# motoko_ice_dragon_x_bldc.net
KiCad netlist of a schematic drawn in EAGLE
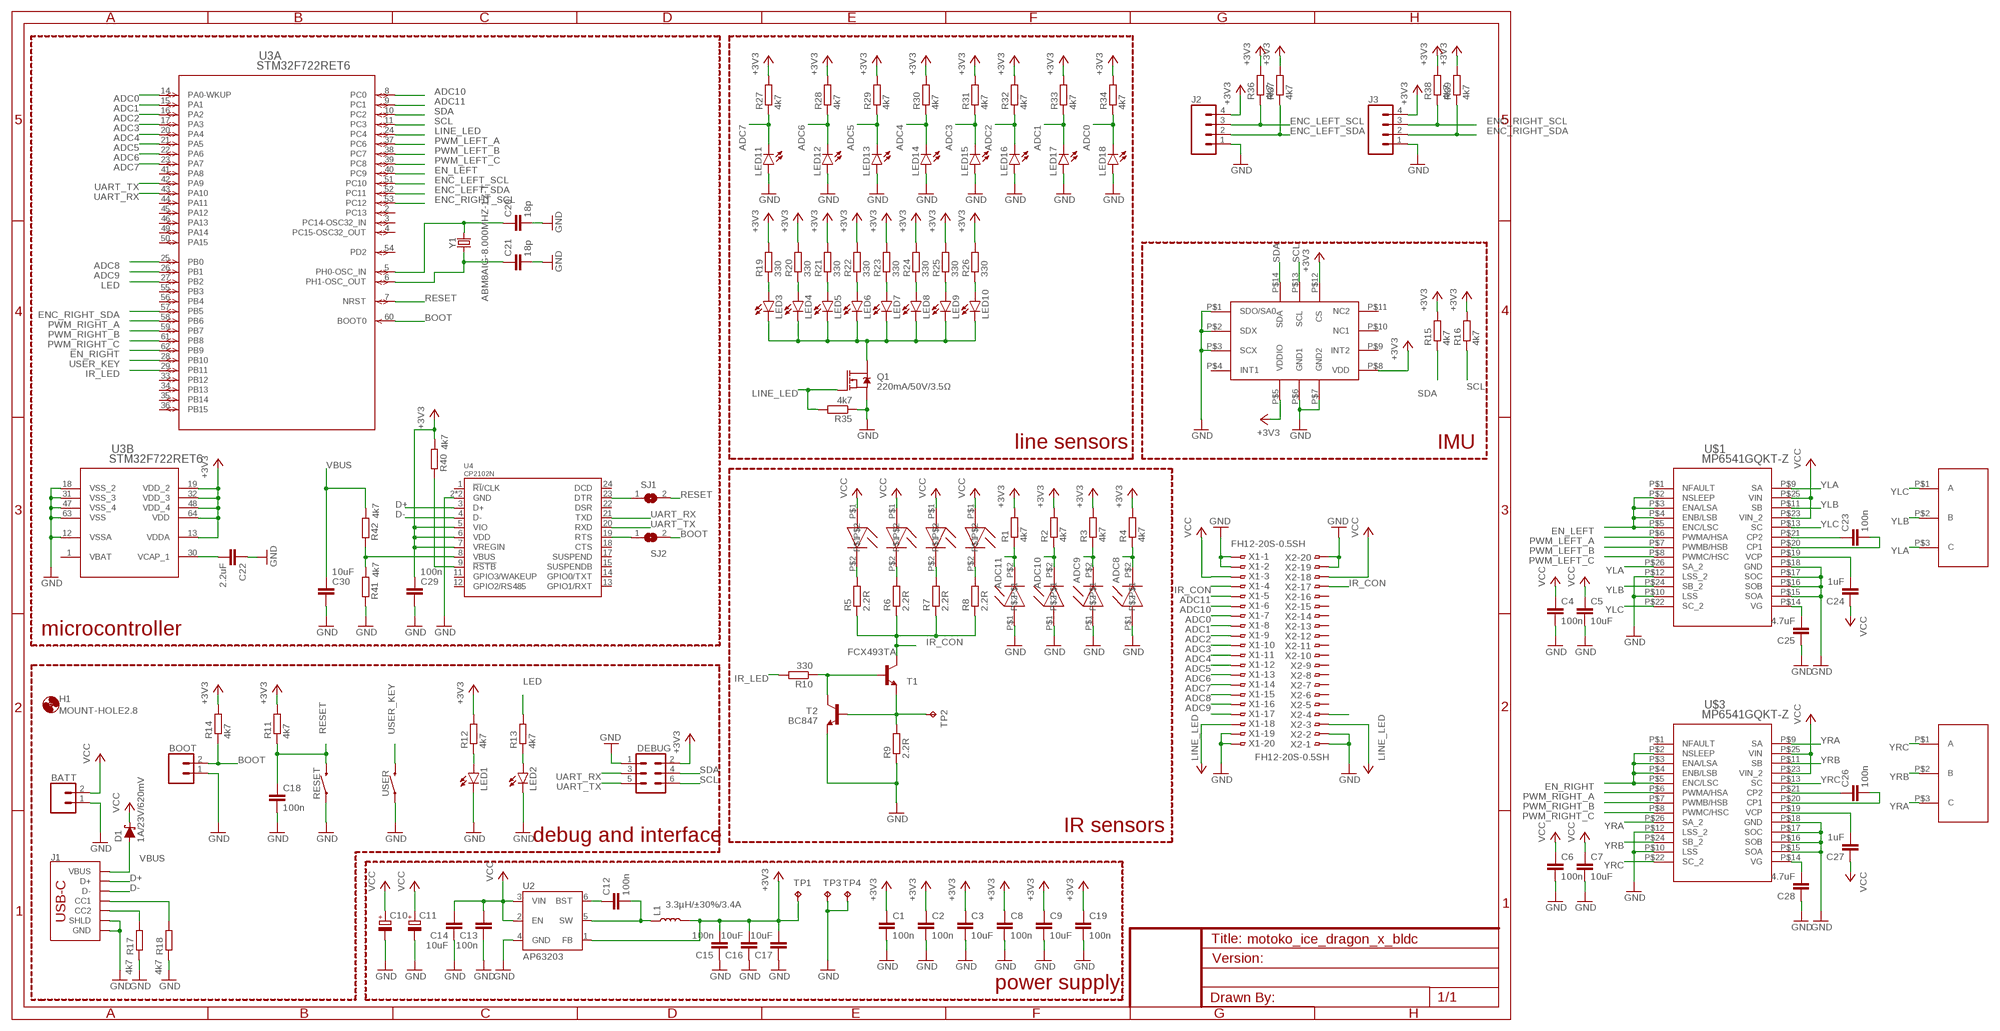
[diagram p0: schematic, sheet 1]

(export (version "E")
  (design (tool "Eeschema 10.0.6"))
  (components
    (comp (ref "BATT")
      (value "CONN_02LOCK_LONGPADS")
      (footprint "eagle-import:1X02_LOCK_LONGPADS")
      (libsource (lib "eagle-import") (part "CONN_02LOCK_LONGPADS"))
    )
    (comp (ref "BOOT")
      (value "CONN_02LOCK_LONGPADS")
      (footprint "eagle-import:1X02_LOCK_LONGPADS")
      (libsource (lib "eagle-import") (part "CONN_02LOCK_LONGPADS"))
    )
    (comp (ref "C1")
      (value "100n")
      (footprint "eagle-import:C0805")
      (libsource (lib "eagle-import") (part "C-EUC0805"))
    )
    (comp (ref "C2")
      (value "100n")
      (footprint "eagle-import:C0805")
      (libsource (lib "eagle-import") (part "C-EUC0805"))
    )
    (comp (ref "C3")
      (value "10uF")
      (footprint "eagle-import:C0805")
      (libsource (lib "eagle-import") (part "C-EUC0805"))
    )
    (comp (ref "C4")
      (value "100n")
      (footprint "eagle-import:C0805")
      (libsource (lib "eagle-import") (part "C-EUC0805"))
    )
    (comp (ref "C5")
      (value "10uF")
      (footprint "eagle-import:C0805")
      (libsource (lib "eagle-import") (part "C-EUC0805"))
    )
    (comp (ref "C6")
      (value "100n")
      (footprint "eagle-import:C0805")
      (libsource (lib "eagle-import") (part "C-EUC0805"))
    )
    (comp (ref "C7")
      (value "10uF")
      (footprint "eagle-import:C0805")
      (libsource (lib "eagle-import") (part "C-EUC0805"))
    )
    (comp (ref "C8")
      (value "100n")
      (footprint "eagle-import:C0805")
      (libsource (lib "eagle-import") (part "C-EUC0805"))
    )
    (comp (ref "C9")
      (value "10uF")
      (footprint "eagle-import:C0805")
      (libsource (lib "eagle-import") (part "C-EUC0805"))
    )
    (comp (ref "C10")
      (value "CPOL-EU140CLH-0810")
      (footprint "eagle-import:140CLH-0810")
      (libsource (lib "eagle-import") (part "CPOL-EU140CLH-0810"))
    )
    (comp (ref "C11")
      (value "CPOL-EU140CLH-0810")
      (footprint "eagle-import:140CLH-0810")
      (libsource (lib "eagle-import") (part "CPOL-EU140CLH-0810"))
    )
    (comp (ref "C12")
      (value "100n")
      (footprint "eagle-import:C0805")
      (libsource (lib "eagle-import") (part "C-EUC0805"))
    )
    (comp (ref "C13")
      (value "100n")
      (footprint "eagle-import:C0805")
      (libsource (lib "eagle-import") (part "C-EUC0805"))
    )
    (comp (ref "C14")
      (value "10uF")
      (footprint "eagle-import:C0805")
      (libsource (lib "eagle-import") (part "C-EUC0805"))
    )
    (comp (ref "C15")
      (value "100n")
      (footprint "eagle-import:C0805")
      (libsource (lib "eagle-import") (part "C-EUC0805"))
    )
    (comp (ref "C16")
      (value "10uF")
      (footprint "eagle-import:C0805")
      (libsource (lib "eagle-import") (part "C-EUC0805"))
    )
    (comp (ref "C17")
      (value "10uF")
      (footprint "eagle-import:C0805")
      (libsource (lib "eagle-import") (part "C-EUC0805"))
    )
    (comp (ref "C18")
      (value "100n")
      (footprint "eagle-import:C0805")
      (libsource (lib "eagle-import") (part "C-EUC0805"))
    )
    (comp (ref "C19")
      (value "100n")
      (footprint "eagle-import:C0805")
      (libsource (lib "eagle-import") (part "C-EUC0805"))
    )
    (comp (ref "C20")
      (value "18p")
      (footprint "eagle-import:C0805")
      (libsource (lib "eagle-import") (part "C-EUC0805"))
    )
    (comp (ref "C21")
      (value "18p")
      (footprint "eagle-import:C0805")
      (libsource (lib "eagle-import") (part "C-EUC0805"))
    )
    (comp (ref "C22")
      (value "2.2uF")
      (footprint "eagle-import:C0805")
      (libsource (lib "eagle-import") (part "C-EUC0805"))
    )
    (comp (ref "C23")
      (value "100n")
      (footprint "eagle-import:C0805")
      (libsource (lib "eagle-import") (part "C-EUC0805"))
    )
    (comp (ref "C24")
      (value "1uF")
      (footprint "eagle-import:C0805")
      (libsource (lib "eagle-import") (part "C-EUC0805"))
    )
    (comp (ref "C25")
      (value "4.7uF")
      (footprint "eagle-import:C0805")
      (libsource (lib "eagle-import") (part "C-EUC0805"))
    )
    (comp (ref "C26")
      (value "100n")
      (footprint "eagle-import:C0805")
      (libsource (lib "eagle-import") (part "C-EUC0805"))
    )
    (comp (ref "C27")
      (value "1uF")
      (footprint "eagle-import:C0805")
      (libsource (lib "eagle-import") (part "C-EUC0805"))
    )
    (comp (ref "C28")
      (value "4.7uF")
      (footprint "eagle-import:C0805")
      (libsource (lib "eagle-import") (part "C-EUC0805"))
    )
    (comp (ref "C29")
      (value "100n")
      (footprint "eagle-import:C0805")
      (libsource (lib "eagle-import") (part "C-EUC0805"))
    )
    (comp (ref "C30")
      (value "10uF")
      (footprint "eagle-import:C0805")
      (libsource (lib "eagle-import") (part "C-EUC0805"))
    )
    (comp (ref "D1")
      (value "1A/23V/620mV")
      (footprint "eagle-import:SOD-323")
      (libsource (lib "eagle-import") (part "DIODE-SCHOTTKY-BAT20J"))
    )
    (comp (ref "DEBUG")
      (value "FEMALE 2x3")
      (footprint "eagle-import:2X3")
      (libsource (lib "eagle-import") (part "CONN_03X2FEMALE"))
    )
    (comp (ref "H1")
      (value "MOUNT-HOLE2.8")
      (footprint "eagle-import:2,8")
      (libsource (lib "eagle-import") (part "MOUNT-HOLE2.8"))
    )
    (comp (ref "J1")
      (value "640-USB4105-GF-A-120, man. GCT")
      (footprint "eagle-import:USB-C-16P-2LAYER-PADS")
      (libsource (lib "eagle-import") (part "USB_C_2-LAYER_PADS"))
    )
    (comp (ref "J2")
      (value "CONN_04LONGPADS")
      (footprint "eagle-import:1X04_LONGPADS")
      (libsource (lib "eagle-import") (part "CONN_04LONGPADS"))
    )
    (comp (ref "J3")
      (value "CONN_04LONGPADS")
      (footprint "eagle-import:1X04_LONGPADS")
      (libsource (lib "eagle-import") (part "CONN_04LONGPADS"))
    )
    (comp (ref "L1")
      (value "3.3µH/±30%/3.4A")
      (footprint "eagle-import:CR54")
      (libsource (lib "eagle-import") (part "INDUCTOR-CR54-3.3UH"))
    )
    (comp (ref "LED1")
      (value "LEDCHIPLED_1206")
      (footprint "eagle-import:CHIPLED_1206")
      (libsource (lib "eagle-import") (part "LEDCHIPLED_1206"))
    )
    (comp (ref "LED2")
      (value "LEDCHIPLED_1206")
      (footprint "eagle-import:CHIPLED_1206")
      (libsource (lib "eagle-import") (part "LEDCHIPLED_1206"))
    )
    (comp (ref "LED3")
      (value "LEDCHIPLED_1206")
      (footprint "eagle-import:CHIPLED_1206")
      (libsource (lib "eagle-import") (part "LEDCHIPLED_1206"))
    )
    (comp (ref "LED4")
      (value "LEDCHIPLED_1206")
      (footprint "eagle-import:CHIPLED_1206")
      (libsource (lib "eagle-import") (part "LEDCHIPLED_1206"))
    )
    (comp (ref "LED5")
      (value "LEDCHIPLED_1206")
      (footprint "eagle-import:CHIPLED_1206")
      (libsource (lib "eagle-import") (part "LEDCHIPLED_1206"))
    )
    (comp (ref "LED6")
      (value "LEDCHIPLED_1206")
      (footprint "eagle-import:CHIPLED_1206")
      (libsource (lib "eagle-import") (part "LEDCHIPLED_1206"))
    )
    (comp (ref "LED7")
      (value "LEDCHIPLED_1206")
      (footprint "eagle-import:CHIPLED_1206")
      (libsource (lib "eagle-import") (part "LEDCHIPLED_1206"))
    )
    (comp (ref "LED8")
      (value "LEDCHIPLED_1206")
      (footprint "eagle-import:CHIPLED_1206")
      (libsource (lib "eagle-import") (part "LEDCHIPLED_1206"))
    )
    (comp (ref "LED9")
      (value "LEDCHIPLED_1206")
      (footprint "eagle-import:CHIPLED_1206")
      (libsource (lib "eagle-import") (part "LEDCHIPLED_1206"))
    )
    (comp (ref "LED10")
      (value "LEDCHIPLED_1206")
      (footprint "eagle-import:CHIPLED_1206")
      (libsource (lib "eagle-import") (part "LEDCHIPLED_1206"))
    )
    (comp (ref "LED11")
      (value "LEDCHIPLED_1206")
      (footprint "eagle-import:CHIPLED_1206")
      (libsource (lib "eagle-import") (part "LEDCHIPLED_1206"))
    )
    (comp (ref "LED12")
      (value "LEDCHIPLED_1206")
      (footprint "eagle-import:CHIPLED_1206")
      (libsource (lib "eagle-import") (part "LEDCHIPLED_1206"))
    )
    (comp (ref "LED13")
      (value "LEDCHIPLED_1206")
      (footprint "eagle-import:CHIPLED_1206")
      (libsource (lib "eagle-import") (part "LEDCHIPLED_1206"))
    )
    (comp (ref "LED14")
      (value "LEDCHIPLED_1206")
      (footprint "eagle-import:CHIPLED_1206")
      (libsource (lib "eagle-import") (part "LEDCHIPLED_1206"))
    )
    (comp (ref "LED15")
      (value "LEDCHIPLED_1206")
      (footprint "eagle-import:CHIPLED_1206")
      (libsource (lib "eagle-import") (part "LEDCHIPLED_1206"))
    )
    (comp (ref "LED16")
      (value "LEDCHIPLED_1206")
      (footprint "eagle-import:CHIPLED_1206")
      (libsource (lib "eagle-import") (part "LEDCHIPLED_1206"))
    )
    (comp (ref "LED17")
      (value "LEDCHIPLED_1206")
      (footprint "eagle-import:CHIPLED_1206")
      (libsource (lib "eagle-import") (part "LEDCHIPLED_1206"))
    )
    (comp (ref "LED18")
      (value "LEDCHIPLED_1206")
      (footprint "eagle-import:CHIPLED_1206")
      (libsource (lib "eagle-import") (part "LEDCHIPLED_1206"))
    )
    (comp (ref "Q1")
      (value "220mA/50V/3.5Ω")
      (footprint "eagle-import:SOT23-3")
      (libsource (lib "eagle-import") (part "MOSFET-NCH-BSS138"))
    )
    (comp (ref "R1")
      (value "4k7")
      (footprint "eagle-import:M0805")
      (libsource (lib "eagle-import") (part "R-EU_M0805"))
    )
    (comp (ref "R2")
      (value "4k7")
      (footprint "eagle-import:M0805")
      (libsource (lib "eagle-import") (part "R-EU_M0805"))
    )
    (comp (ref "R3")
      (value "4k7")
      (footprint "eagle-import:M0805")
      (libsource (lib "eagle-import") (part "R-EU_M0805"))
    )
    (comp (ref "R4")
      (value "4k7")
      (footprint "eagle-import:M0805")
      (libsource (lib "eagle-import") (part "R-EU_M0805"))
    )
    (comp (ref "R5")
      (value "2.2R")
      (footprint "eagle-import:M0805")
      (libsource (lib "eagle-import") (part "R-EU_M0805"))
    )
    (comp (ref "R6")
      (value "2.2R")
      (footprint "eagle-import:M0805")
      (libsource (lib "eagle-import") (part "R-EU_M0805"))
    )
    (comp (ref "R7")
      (value "2.2R")
      (footprint "eagle-import:M0805")
      (libsource (lib "eagle-import") (part "R-EU_M0805"))
    )
    (comp (ref "R8")
      (value "2.2R")
      (footprint "eagle-import:M0805")
      (libsource (lib "eagle-import") (part "R-EU_M0805"))
    )
    (comp (ref "R9")
      (value "2.2R")
      (footprint "eagle-import:M0805")
      (libsource (lib "eagle-import") (part "R-EU_M0805"))
    )
    (comp (ref "R10")
      (value "330")
      (footprint "eagle-import:M0805")
      (libsource (lib "eagle-import") (part "R-EU_M0805"))
    )
    (comp (ref "R11")
      (value "4k7")
      (footprint "eagle-import:M0805")
      (libsource (lib "eagle-import") (part "R-EU_M0805"))
    )
    (comp (ref "R12")
      (value "4k7")
      (footprint "eagle-import:M0805")
      (libsource (lib "eagle-import") (part "R-EU_M0805"))
    )
    (comp (ref "R13")
      (value "4k7")
      (footprint "eagle-import:M0805")
      (libsource (lib "eagle-import") (part "R-EU_M0805"))
    )
    (comp (ref "R14")
      (value "4k7")
      (footprint "eagle-import:M0805")
      (libsource (lib "eagle-import") (part "R-EU_M0805"))
    )
    (comp (ref "R15")
      (value "4k7")
      (footprint "eagle-import:M0805")
      (libsource (lib "eagle-import") (part "R-EU_M0805"))
    )
    (comp (ref "R16")
      (value "4k7")
      (footprint "eagle-import:M0805")
      (libsource (lib "eagle-import") (part "R-EU_M0805"))
    )
    (comp (ref "R17")
      (value "4k7")
      (footprint "eagle-import:M0805")
      (libsource (lib "eagle-import") (part "R-EU_M0805"))
    )
    (comp (ref "R18")
      (value "4k7")
      (footprint "eagle-import:M0805")
      (libsource (lib "eagle-import") (part "R-EU_M0805"))
    )
    (comp (ref "R19")
      (value "330")
      (footprint "eagle-import:M0805")
      (libsource (lib "eagle-import") (part "R-EU_M0805"))
    )
    (comp (ref "R20")
      (value "330")
      (footprint "eagle-import:M0805")
      (libsource (lib "eagle-import") (part "R-EU_M0805"))
    )
    (comp (ref "R21")
      (value "330")
      (footprint "eagle-import:M0805")
      (libsource (lib "eagle-import") (part "R-EU_M0805"))
    )
    (comp (ref "R22")
      (value "330")
      (footprint "eagle-import:M0805")
      (libsource (lib "eagle-import") (part "R-EU_M0805"))
    )
    (comp (ref "R23")
      (value "330")
      (footprint "eagle-import:M0805")
      (libsource (lib "eagle-import") (part "R-EU_M0805"))
    )
    (comp (ref "R24")
      (value "330")
      (footprint "eagle-import:M0805")
      (libsource (lib "eagle-import") (part "R-EU_M0805"))
    )
    (comp (ref "R25")
      (value "330")
      (footprint "eagle-import:M0805")
      (libsource (lib "eagle-import") (part "R-EU_M0805"))
    )
    (comp (ref "R26")
      (value "330")
      (footprint "eagle-import:M0805")
      (libsource (lib "eagle-import") (part "R-EU_M0805"))
    )
    (comp (ref "R27")
      (value "4k7")
      (footprint "eagle-import:M0805")
      (libsource (lib "eagle-import") (part "R-EU_M0805"))
    )
    (comp (ref "R28")
      (value "4k7")
      (footprint "eagle-import:M0805")
      (libsource (lib "eagle-import") (part "R-EU_M0805"))
    )
    (comp (ref "R29")
      (value "4k7")
      (footprint "eagle-import:M0805")
      (libsource (lib "eagle-import") (part "R-EU_M0805"))
    )
    (comp (ref "R30")
      (value "4k7")
      (footprint "eagle-import:M0805")
      (libsource (lib "eagle-import") (part "R-EU_M0805"))
    )
    (comp (ref "R31")
      (value "4k7")
      (footprint "eagle-import:M0805")
      (libsource (lib "eagle-import") (part "R-EU_M0805"))
    )
    (comp (ref "R32")
      (value "4k7")
      (footprint "eagle-import:M0805")
      (libsource (lib "eagle-import") (part "R-EU_M0805"))
    )
    (comp (ref "R33")
      (value "4k7")
      (footprint "eagle-import:M0805")
      (libsource (lib "eagle-import") (part "R-EU_M0805"))
    )
    (comp (ref "R34")
      (value "4k7")
      (footprint "eagle-import:M0805")
      (libsource (lib "eagle-import") (part "R-EU_M0805"))
    )
    (comp (ref "R35")
      (value "4k7")
      (footprint "eagle-import:M0805")
      (libsource (lib "eagle-import") (part "R-EU_M0805"))
    )
    (comp (ref "R36")
      (value "4k7")
      (footprint "eagle-import:M0805")
      (libsource (lib "eagle-import") (part "R-EU_M0805"))
    )
    (comp (ref "R37")
      (value "4k7")
      (footprint "eagle-import:M0805")
      (libsource (lib "eagle-import") (part "R-EU_M0805"))
    )
    (comp (ref "R38")
      (value "4k7")
      (footprint "eagle-import:M0805")
      (libsource (lib "eagle-import") (part "R-EU_M0805"))
    )
    (comp (ref "R39")
      (value "4k7")
      (footprint "eagle-import:M0805")
      (libsource (lib "eagle-import") (part "R-EU_M0805"))
    )
    (comp (ref "R40")
      (value "4k7")
      (footprint "eagle-import:M0805")
      (libsource (lib "eagle-import") (part "R-EU_M0805"))
    )
    (comp (ref "R41")
      (value "4k7")
      (footprint "eagle-import:M0805")
      (libsource (lib "eagle-import") (part "R-EU_M0805"))
    )
    (comp (ref "R42")
      (value "4k7")
      (footprint "eagle-import:M0805")
      (libsource (lib "eagle-import") (part "R-EU_M0805"))
    )
    (comp (ref "RESET")
      (value "MOMENTARY-SWITCH-SPST-SMD-6.2MM-TALL")
      (footprint "eagle-import:TACTILE_SWITCH_SMD_6.2MM_TALL")
      (libsource (lib "eagle-import") (part "MOMENTARY-SWITCH-SPST-SMD-6.2MM-TALL"))
    )
    (comp (ref "SJ1") (value "SJ") (footprint "eagle-import:SJ") (libsource (lib "eagle-import") (part "SJ")))
    (comp (ref "SJ2") (value "SJ") (footprint "eagle-import:SJ") (libsource (lib "eagle-import") (part "SJ")))
    (comp (ref "T1")
      (value "FCX493TA")
      (footprint "eagle-import:SOT89-BCE")
      (libsource (lib "eagle-import") (part "-NPN-SOT89-BCE"))
    )
    (comp (ref "T2")
      (value "BC847")
      (footprint "eagle-import:SOT23")
      (libsource (lib "eagle-import") (part "BC847"))
    )
    (comp (ref "TP1")
      (value "TPB1,27")
      (footprint "eagle-import:B1,27")
      (libsource (lib "eagle-import") (part "TPB1,27"))
    )
    (comp (ref "TP2")
      (value "TPB1,27")
      (footprint "eagle-import:B1,27")
      (libsource (lib "eagle-import") (part "TPB1,27"))
    )
    (comp (ref "TP3")
      (value "TPB1,27")
      (footprint "eagle-import:B1,27")
      (libsource (lib "eagle-import") (part "TPB1,27"))
    )
    (comp (ref "TP4")
      (value "TPB1,27")
      (footprint "eagle-import:B1,27")
      (libsource (lib "eagle-import") (part "TPB1,27"))
    )
    (comp (ref "U$1")
      (value "MP6541GQKT-Z")
      (footprint "eagle-import:TQFN-26")
      (libsource (lib "eagle-import") (part "MP6541GQKT-Z"))
    )
    (comp (ref "U$2")
      (value "BRUSHLESS_GIMBAL_MOTOR_WHEEL")
      (footprint "eagle-import:BRUSHLESS_GIMBAL_MOTOR_WHEEL")
      (libsource (lib "eagle-import") (part "BRUSHLESS_GIMBAL_MOTOR_WHEEL"))
    )
    (comp (ref "U$3")
      (value "MP6541GQKT-Z")
      (footprint "eagle-import:TQFN-26")
      (libsource (lib "eagle-import") (part "MP6541GQKT-Z"))
    )
    (comp (ref "U$4")
      (value "BRUSHLESS_GIMBAL_MOTOR_WHEEL")
      (footprint "eagle-import:BRUSHLESS_GIMBAL_MOTOR_WHEEL")
      (libsource (lib "eagle-import") (part "BRUSHLESS_GIMBAL_MOTOR_WHEEL"))
    )
    (comp (ref "U$6")
      (value "LSM6DSM")
      (footprint "eagle-import:LGA14L")
      (libsource (lib "eagle-import") (part "LSM6DSM"))
    )
    (comp (ref "U$7")
      (value "LED_5MM_AXIAL")
      (footprint "eagle-import:LED_5MM_AXIAL")
      (libsource (lib "eagle-import") (part "LED_5MM_AXIAL"))
    )
    (comp (ref "U$8")
      (value "LED_5MM_AXIAL")
      (footprint "eagle-import:LED_5MM_AXIAL")
      (libsource (lib "eagle-import") (part "LED_5MM_AXIAL"))
    )
    (comp (ref "U$9")
      (value "LED_5MM_AXIAL")
      (footprint "eagle-import:LED_5MM_AXIAL")
      (libsource (lib "eagle-import") (part "LED_5MM_AXIAL"))
    )
    (comp (ref "U$10")
      (value "LED_5MM_AXIAL")
      (footprint "eagle-import:LED_5MM_AXIAL")
      (libsource (lib "eagle-import") (part "LED_5MM_AXIAL"))
    )
    (comp (ref "U$11")
      (value "LED_5MM_AXIAL")
      (footprint "eagle-import:LED_5MM_AXIAL")
      (libsource (lib "eagle-import") (part "LED_5MM_AXIAL"))
    )
    (comp (ref "U$12")
      (value "LED_5MM_AXIAL")
      (footprint "eagle-import:LED_5MM_AXIAL")
      (fields (field (name "SPICEPREFIX") "B"))
      (libsource (lib "eagle-import") (part "LED_5MM_AXIAL"))
    )
    (comp (ref "U$13")
      (value "LED_5MM_AXIAL")
      (footprint "eagle-import:LED_5MM_AXIAL")
      (libsource (lib "eagle-import") (part "LED_5MM_AXIAL"))
    )
    (comp (ref "U$14")
      (value "LED_5MM_AXIAL")
      (footprint "eagle-import:LED_5MM_AXIAL")
      (libsource (lib "eagle-import") (part "LED_5MM_AXIAL"))
    )
    (comp (ref "U2")
      (value "AP63203")
      (footprint "eagle-import:SOT23-6")
      (libsource (lib "eagle-import") (part "AP63203"))
    )
    (comp (ref "U3")
      (value "STM32F722RET6")
      (footprint "eagle-import:LQFP64-10X10MM")
      (fields (field (name "COPYRIGHT") "Copyright (C) 2024 Ultra Librarian. All rights reserved."))
      (libsource (lib "eagle-import") (part "STM32F722RET6"))
    )
    (comp (ref "U4")
      (value "CP2102N")
      (footprint "eagle-import:QFN24")
      (libsource (lib "eagle-import") (part "CP2102N"))
    )
    (comp (ref "USER")
      (value "MOMENTARY-SWITCH-SPST-SMD-6.2MM-TALL")
      (footprint "eagle-import:TACTILE_SWITCH_SMD_6.2MM_TALL")
      (libsource (lib "eagle-import") (part "MOMENTARY-SWITCH-SPST-SMD-6.2MM-TALL"))
    )
    (comp (ref "X1")
      (value "FH12-20S-0.5SH")
      (footprint "eagle-import:FH12-20S-0.5SH")
      (fields (field (name "MPN") "FH12-20S-0.5SH(55)"))
      (libsource (lib "eagle-import") (part "FH12-20S-0.5SH"))
    )
    (comp (ref "X2")
      (value "FH12-20S-0.5SH")
      (footprint "eagle-import:FH12-20S-0.5SH")
      (fields (field (name "MPN") "FH12-20S-0.5SH(55)"))
      (libsource (lib "eagle-import") (part "FH12-20S-0.5SH"))
    )
    (comp (ref "Y1")
      (value "ABM8AIG-8.000MHZ-1Z-T")
      (footprint "eagle-import:CRYSTAL-SMD-3.2X2.5MM")
      (libsource (lib "eagle-import") (part "CRYSTALSMD-3.2X2.5"))
    )
  )
  (nets
    (net (code "1") (name "+3V3") (class "Default")
      (node (ref "C1") (pin "1") (pinfunction "1_1") (pintype "passive"))
      (node (ref "C15") (pin "2") (pinfunction "2_2") (pintype "passive"))
      (node (ref "C16") (pin "2") (pinfunction "2_2") (pintype "passive"))
      (node (ref "C17") (pin "2") (pinfunction "2_2") (pintype "passive"))
      (node (ref "C19") (pin "1") (pinfunction "1_1") (pintype "passive"))
      (node (ref "C2") (pin "1") (pinfunction "1_1") (pintype "passive"))
      (node (ref "C29") (pin "1") (pinfunction "1_1") (pintype "passive"))
      (node (ref "C3") (pin "1") (pinfunction "1_1") (pintype "passive"))
      (node (ref "C8") (pin "1") (pinfunction "1_1") (pintype "passive"))
      (node (ref "C9") (pin "1") (pinfunction "1_1") (pintype "passive"))
      (node (ref "DEBUG") (pin "2") (pinfunction "2_2") (pintype "bidirectional"))
      (node (ref "J2") (pin "4") (pinfunction "4_4") (pintype "passive"))
      (node (ref "J3") (pin "4") (pinfunction "4_4") (pintype "passive"))
      (node (ref "L1") (pin "P$2") (pinfunction "2_P$2") (pintype "passive"))
      (node (ref "R1") (pin "2") (pinfunction "2_2") (pintype "passive"))
      (node (ref "R11") (pin "2") (pinfunction "2_2") (pintype "passive"))
      (node (ref "R12") (pin "2") (pinfunction "2_2") (pintype "passive"))
      (node (ref "R14") (pin "2") (pinfunction "2_2") (pintype "passive"))
      (node (ref "R15") (pin "2") (pinfunction "2_2") (pintype "passive"))
      (node (ref "R16") (pin "2") (pinfunction "2_2") (pintype "passive"))
      (node (ref "R19") (pin "2") (pinfunction "2_2") (pintype "passive"))
      (node (ref "R2") (pin "2") (pinfunction "2_2") (pintype "passive"))
      (node (ref "R20") (pin "2") (pinfunction "2_2") (pintype "passive"))
      (node (ref "R21") (pin "2") (pinfunction "2_2") (pintype "passive"))
      (node (ref "R22") (pin "2") (pinfunction "2_2") (pintype "passive"))
      (node (ref "R23") (pin "2") (pinfunction "2_2") (pintype "passive"))
      (node (ref "R24") (pin "2") (pinfunction "2_2") (pintype "passive"))
      (node (ref "R25") (pin "2") (pinfunction "2_2") (pintype "passive"))
      (node (ref "R26") (pin "2") (pinfunction "2_2") (pintype "passive"))
      (node (ref "R27") (pin "2") (pinfunction "2_2") (pintype "passive"))
      (node (ref "R28") (pin "2") (pinfunction "2_2") (pintype "passive"))
      (node (ref "R29") (pin "2") (pinfunction "2_2") (pintype "passive"))
      (node (ref "R3") (pin "2") (pinfunction "2_2") (pintype "passive"))
      (node (ref "R30") (pin "2") (pinfunction "2_2") (pintype "passive"))
      (node (ref "R31") (pin "2") (pinfunction "2_2") (pintype "passive"))
      (node (ref "R32") (pin "2") (pinfunction "2_2") (pintype "passive"))
      (node (ref "R33") (pin "2") (pinfunction "2_2") (pintype "passive"))
      (node (ref "R34") (pin "2") (pinfunction "2_2") (pintype "passive"))
      (node (ref "R36") (pin "2") (pinfunction "2_2") (pintype "passive"))
      (node (ref "R37") (pin "2") (pinfunction "2_2") (pintype "passive"))
      (node (ref "R38") (pin "2") (pinfunction "2_2") (pintype "passive"))
      (node (ref "R39") (pin "2") (pinfunction "2_2") (pintype "passive"))
      (node (ref "R4") (pin "2") (pinfunction "2_2") (pintype "passive"))
      (node (ref "R40") (pin "1") (pinfunction "1_1") (pintype "passive"))
      (node (ref "TP1") (pin "TP") (pinfunction "TP_TP") (pintype "input"))
      (node (ref "U$6") (pin "P$12") (pinfunction "CS_P$12") (pintype "bidirectional"))
      (node (ref "U$6") (pin "P$5") (pinfunction "VDDIO_P$5") (pintype "bidirectional"))
      (node (ref "U$6") (pin "P$8") (pinfunction "VDD_P$8") (pintype "bidirectional"))
      (node (ref "U2") (pin "1") (pinfunction "FB_1") (pintype "bidirectional"))
      (node (ref "U3") (pin "13") (pinfunction "VDDA_13") (pintype "power_in"))
      (node (ref "U3") (pin "19") (pinfunction "VDD_2_19") (pintype "power_in"))
      (node (ref "U3") (pin "32") (pinfunction "VDD_3_32") (pintype "power_in"))
      (node (ref "U3") (pin "48") (pinfunction "VDD_4_48") (pintype "power_in"))
      (node (ref "U3") (pin "64") (pinfunction "VDD_64") (pintype "power_in"))
      (node (ref "U4") (pin "5") (pinfunction "VIO_5") (pintype "bidirectional"))
      (node (ref "U4") (pin "6") (pinfunction "VDD_6") (pintype "bidirectional"))
      (node (ref "U4") (pin "7") (pinfunction "VREGIN_7") (pintype "bidirectional"))
      (node (ref "X1") (pin "18") (pinfunction "1_18") (pintype "passive"))
      (node (ref "X2") (pin "3") (pinfunction "1_3") (pintype "passive"))
    )
    (net (code "2") (name "/ADC0") (class "Default")
      (node (ref "LED18") (pin "C") (pinfunction "C_C") (pintype "passive"))
      (node (ref "R34") (pin "1") (pinfunction "1_1") (pintype "passive"))
      (node (ref "U3") (pin "14") (pinfunction "PA0-WKUP_14") (pintype "bidirectional"))
      (node (ref "X1") (pin "7") (pinfunction "1_7") (pintype "passive"))
    )
    (net (code "3") (name "/ADC1") (class "Default")
      (node (ref "LED17") (pin "C") (pinfunction "C_C") (pintype "passive"))
      (node (ref "R33") (pin "1") (pinfunction "1_1") (pintype "passive"))
      (node (ref "U3") (pin "15") (pinfunction "PA1_15") (pintype "bidirectional"))
      (node (ref "X1") (pin "8") (pinfunction "1_8") (pintype "passive"))
    )
    (net (code "4") (name "/ADC2") (class "Default")
      (node (ref "LED16") (pin "C") (pinfunction "C_C") (pintype "passive"))
      (node (ref "R32") (pin "1") (pinfunction "1_1") (pintype "passive"))
      (node (ref "U3") (pin "16") (pinfunction "PA2_16") (pintype "bidirectional"))
      (node (ref "X1") (pin "9") (pinfunction "1_9") (pintype "passive"))
    )
    (net (code "5") (name "/ADC3") (class "Default")
      (node (ref "LED15") (pin "C") (pinfunction "C_C") (pintype "passive"))
      (node (ref "R31") (pin "1") (pinfunction "1_1") (pintype "passive"))
      (node (ref "U3") (pin "17") (pinfunction "PA3_17") (pintype "bidirectional"))
      (node (ref "X1") (pin "10") (pinfunction "1_10") (pintype "passive"))
    )
    (net (code "6") (name "/ADC4") (class "Default")
      (node (ref "LED14") (pin "C") (pinfunction "C_C") (pintype "passive"))
      (node (ref "R30") (pin "1") (pinfunction "1_1") (pintype "passive"))
      (node (ref "U3") (pin "20") (pinfunction "PA4_20") (pintype "bidirectional"))
      (node (ref "X1") (pin "11") (pinfunction "1_11") (pintype "passive"))
    )
    (net (code "7") (name "/ADC5") (class "Default")
      (node (ref "LED13") (pin "C") (pinfunction "C_C") (pintype "passive"))
      (node (ref "R29") (pin "1") (pinfunction "1_1") (pintype "passive"))
      (node (ref "U3") (pin "21") (pinfunction "PA5_21") (pintype "bidirectional"))
      (node (ref "X1") (pin "12") (pinfunction "1_12") (pintype "passive"))
    )
    (net (code "8") (name "/ADC6") (class "Default")
      (node (ref "LED12") (pin "C") (pinfunction "C_C") (pintype "passive"))
      (node (ref "R28") (pin "1") (pinfunction "1_1") (pintype "passive"))
      (node (ref "U3") (pin "22") (pinfunction "PA6_22") (pintype "bidirectional"))
      (node (ref "X1") (pin "13") (pinfunction "1_13") (pintype "passive"))
    )
    (net (code "9") (name "/ADC7") (class "Default")
      (node (ref "LED11") (pin "C") (pinfunction "C_C") (pintype "passive"))
      (node (ref "R27") (pin "1") (pinfunction "1_1") (pintype "passive"))
      (node (ref "U3") (pin "23") (pinfunction "PA7_23") (pintype "bidirectional"))
      (node (ref "X1") (pin "14") (pinfunction "1_14") (pintype "passive"))
    )
    (net (code "10") (name "/ADC8") (class "Default")
      (node (ref "R4") (pin "1") (pinfunction "1_1") (pintype "passive"))
      (node (ref "U$7") (pin "P$2") (pinfunction "P$2_P$2") (pintype "bidirectional"))
      (node (ref "U3") (pin "25") (pinfunction "PB0_25") (pintype "bidirectional"))
      (node (ref "X1") (pin "15") (pinfunction "1_15") (pintype "passive"))
    )
    (net (code "11") (name "/ADC9") (class "Default")
      (node (ref "R3") (pin "1") (pinfunction "1_1") (pintype "passive"))
      (node (ref "U$11") (pin "P$2") (pinfunction "P$2_P$2") (pintype "bidirectional"))
      (node (ref "U3") (pin "26") (pinfunction "PB1_26") (pintype "bidirectional"))
      (node (ref "X1") (pin "16") (pinfunction "1_16") (pintype "passive"))
    )
    (net (code "12") (name "/ADC10") (class "Default")
      (node (ref "R2") (pin "1") (pinfunction "1_1") (pintype "passive"))
      (node (ref "U$14") (pin "P$2") (pinfunction "P$2_P$2") (pintype "bidirectional"))
      (node (ref "U3") (pin "8") (pinfunction "PC0_8") (pintype "bidirectional"))
      (node (ref "X1") (pin "6") (pinfunction "1_6") (pintype "passive"))
    )
    (net (code "13") (name "/ADC11") (class "Default")
      (node (ref "R1") (pin "1") (pinfunction "1_1") (pintype "passive"))
      (node (ref "U$9") (pin "P$2") (pinfunction "P$2_P$2") (pintype "bidirectional"))
      (node (ref "U3") (pin "9") (pinfunction "PC1_9") (pintype "bidirectional"))
      (node (ref "X1") (pin "5") (pinfunction "1_5") (pintype "passive"))
    )
    (net (code "14") (name "/BOOT") (class "Default")
      (node (ref "BOOT") (pin "2") (pinfunction "2_2") (pintype "passive"))
      (node (ref "R14") (pin "1") (pinfunction "1_1") (pintype "passive"))
      (node (ref "SJ2") (pin "2") (pinfunction "2_2") (pintype "passive"))
      (node (ref "U3") (pin "60") (pinfunction "BOOT0_60") (pintype "input"))
    )
    (net (code "15") (name "/D+") (class "Default")
      (node (ref "J1") (pin "A6") (pinfunction "D+_A6") (pintype "bidirectional"))
      (node (ref "J1") (pin "B6") (pinfunction "D+_B6") (pintype "bidirectional"))
      (node (ref "U4") (pin "3") (pinfunction "D+_3") (pintype "bidirectional"))
    )
    (net (code "16") (name "/D-") (class "Default")
      (node (ref "J1") (pin "A7") (pinfunction "D-_A7") (pintype "bidirectional"))
      (node (ref "J1") (pin "B7") (pinfunction "D-_B7") (pintype "bidirectional"))
      (node (ref "U4") (pin "4") (pinfunction "D-_4") (pintype "bidirectional"))
    )
    (net (code "17") (name "/ENC_LEFT_SCL") (class "Default")
      (node (ref "J2") (pin "3") (pinfunction "3_3") (pintype "passive"))
      (node (ref "R36") (pin "1") (pinfunction "1_1") (pintype "passive"))
      (node (ref "U3") (pin "51") (pinfunction "PC10_51") (pintype "bidirectional"))
    )
    (net (code "18") (name "/ENC_LEFT_SDA") (class "Default")
      (node (ref "J2") (pin "2") (pinfunction "2_2") (pintype "passive"))
      (node (ref "R37") (pin "1") (pinfunction "1_1") (pintype "passive"))
      (node (ref "U3") (pin "52") (pinfunction "PC11_52") (pintype "bidirectional"))
    )
    (net (code "19") (name "/ENC_RIGHT_SCL") (class "Default")
      (node (ref "J3") (pin "3") (pinfunction "3_3") (pintype "passive"))
      (node (ref "R38") (pin "1") (pinfunction "1_1") (pintype "passive"))
      (node (ref "U3") (pin "53") (pinfunction "PC12_53") (pintype "bidirectional"))
    )
    (net (code "20") (name "/ENC_RIGHT_SDA") (class "Default")
      (node (ref "J3") (pin "2") (pinfunction "2_2") (pintype "passive"))
      (node (ref "R39") (pin "1") (pinfunction "1_1") (pintype "passive"))
      (node (ref "U3") (pin "57") (pinfunction "PB5_57") (pintype "bidirectional"))
    )
    (net (code "21") (name "/EN_LEFT") (class "Default")
      (node (ref "U$1") (pin "P$2") (pinfunction "NSLEEP_P$2") (pintype "input"))
      (node (ref "U$1") (pin "P$3") (pinfunction "ENA/LSA_P$3") (pintype "passive"))
      (node (ref "U$1") (pin "P$4") (pinfunction "ENB/LSB_P$4") (pintype "passive"))
      (node (ref "U$1") (pin "P$5") (pinfunction "ENC/LSC_P$5") (pintype "passive"))
      (node (ref "U3") (pin "40") (pinfunction "PC9_40") (pintype "bidirectional"))
    )
    (net (code "22") (name "/EN_RIGHT") (class "Default")
      (node (ref "U$3") (pin "P$2") (pinfunction "NSLEEP_P$2") (pintype "input"))
      (node (ref "U$3") (pin "P$3") (pinfunction "ENA/LSA_P$3") (pintype "passive"))
      (node (ref "U$3") (pin "P$4") (pinfunction "ENB/LSB_P$4") (pintype "passive"))
      (node (ref "U$3") (pin "P$5") (pinfunction "ENC/LSC_P$5") (pintype "passive"))
      (node (ref "U3") (pin "62") (pinfunction "PB9_62") (pintype "bidirectional"))
    )
    (net (code "23") (name "/IR_CON") (class "Default")
      (node (ref "R5") (pin "1") (pinfunction "1_1") (pintype "passive"))
      (node (ref "R6") (pin "1") (pinfunction "1_1") (pintype "passive"))
      (node (ref "R7") (pin "1") (pinfunction "1_1") (pintype "passive"))
      (node (ref "R8") (pin "1") (pinfunction "1_1") (pintype "passive"))
      (node (ref "T1") (pin "C") (pinfunction "C_C") (pintype "passive"))
      (node (ref "X1") (pin "4") (pinfunction "1_4") (pintype "passive"))
      (node (ref "X2") (pin "17") (pinfunction "1_17") (pintype "passive"))
    )
    (net (code "24") (name "/IR_LED") (class "Default")
      (node (ref "R10") (pin "2") (pinfunction "2_2") (pintype "passive"))
      (node (ref "U3") (pin "29") (pinfunction "PB11_29") (pintype "bidirectional"))
    )
    (net (code "25") (name "/LED") (class "Default")
      (node (ref "R13") (pin "2") (pinfunction "2_2") (pintype "passive"))
      (node (ref "U3") (pin "27") (pinfunction "PB2_27") (pintype "bidirectional"))
    )
    (net (code "26") (name "/LINE_LED") (class "Default")
      (node (ref "Q1") (pin "1") (pinfunction "G_1") (pintype "bidirectional"))
      (node (ref "R35") (pin "2") (pinfunction "2_2") (pintype "passive"))
      (node (ref "U3") (pin "24") (pinfunction "PC4_24") (pintype "bidirectional"))
      (node (ref "X1") (pin "17") (pinfunction "1_17") (pintype "passive"))
      (node (ref "X2") (pin "4") (pinfunction "1_4") (pintype "passive"))
    )
    (net (code "27") (name "/PWM_LEFT_A") (class "Default")
      (node (ref "U$1") (pin "P$6") (pinfunction "PWMA/HSA_P$6") (pintype "passive"))
      (node (ref "U3") (pin "37") (pinfunction "PC6_37") (pintype "bidirectional"))
    )
    (net (code "28") (name "/PWM_LEFT_B") (class "Default")
      (node (ref "U$1") (pin "P$7") (pinfunction "PWMB/HSB_P$7") (pintype "passive"))
      (node (ref "U3") (pin "38") (pinfunction "PC7_38") (pintype "bidirectional"))
    )
    (net (code "29") (name "/PWM_LEFT_C") (class "Default")
      (node (ref "U$1") (pin "P$8") (pinfunction "PWMC/HSC_P$8") (pintype "passive"))
      (node (ref "U3") (pin "39") (pinfunction "PC8_39") (pintype "bidirectional"))
    )
    (net (code "30") (name "/PWM_RIGHT_A") (class "Default")
      (node (ref "U$3") (pin "P$6") (pinfunction "PWMA/HSA_P$6") (pintype "passive"))
      (node (ref "U3") (pin "58") (pinfunction "PB6_58") (pintype "bidirectional"))
    )
    (net (code "31") (name "/PWM_RIGHT_B") (class "Default")
      (node (ref "U$3") (pin "P$7") (pinfunction "PWMB/HSB_P$7") (pintype "passive"))
      (node (ref "U3") (pin "59") (pinfunction "PB7_59") (pintype "bidirectional"))
    )
    (net (code "32") (name "/PWM_RIGHT_C") (class "Default")
      (node (ref "U$3") (pin "P$8") (pinfunction "PWMC/HSC_P$8") (pintype "passive"))
      (node (ref "U3") (pin "61") (pinfunction "PB8_61") (pintype "bidirectional"))
    )
    (net (code "33") (name "/RESET") (class "Default")
      (node (ref "C18") (pin "1") (pinfunction "1_1") (pintype "passive"))
      (node (ref "R11") (pin "1") (pinfunction "1_1") (pintype "passive"))
      (node (ref "RESET") (pin "B2") (pinfunction "2_B2") (pintype "passive"))
      (node (ref "SJ1") (pin "2") (pinfunction "2_2") (pintype "passive"))
      (node (ref "U3") (pin "7") (pinfunction "NRST_7") (pintype "bidirectional"))
    )
    (net (code "34") (name "/SCL") (class "Default")
      (node (ref "DEBUG") (pin "6") (pinfunction "6_6") (pintype "bidirectional"))
      (node (ref "R16") (pin "1") (pinfunction "1_1") (pintype "passive"))
      (node (ref "U$6") (pin "P$13") (pinfunction "SCL_P$13") (pintype "bidirectional"))
      (node (ref "U3") (pin "11") (pinfunction "PC3_11") (pintype "bidirectional"))
    )
    (net (code "35") (name "/SDA") (class "Default")
      (node (ref "DEBUG") (pin "4") (pinfunction "4_4") (pintype "bidirectional"))
      (node (ref "R15") (pin "1") (pinfunction "1_1") (pintype "passive"))
      (node (ref "U$6") (pin "P$14") (pinfunction "SDA_P$14") (pintype "bidirectional"))
      (node (ref "U3") (pin "10") (pinfunction "PC2_10") (pintype "bidirectional"))
    )
    (net (code "36") (name "/UART_RX") (class "Default")
      (node (ref "DEBUG") (pin "3") (pinfunction "3_3") (pintype "bidirectional"))
      (node (ref "U3") (pin "43") (pinfunction "PA10_43") (pintype "bidirectional"))
      (node (ref "U4") (pin "21") (pinfunction "TXD_21") (pintype "bidirectional"))
    )
    (net (code "37") (name "/UART_TX") (class "Default")
      (node (ref "DEBUG") (pin "5") (pinfunction "5_5") (pintype "bidirectional"))
      (node (ref "U3") (pin "42") (pinfunction "PA9_42") (pintype "bidirectional"))
      (node (ref "U4") (pin "20") (pinfunction "RXD_20") (pintype "bidirectional"))
    )
    (net (code "38") (name "/USER_KEY") (class "Default")
      (node (ref "U3") (pin "28") (pinfunction "PB10_28") (pintype "bidirectional"))
      (node (ref "USER") (pin "B2") (pinfunction "2_B2") (pintype "passive"))
    )
    (net (code "39") (name "/VBAT") (class "Default")
      (node (ref "U3") (pin "1") (pinfunction "VBAT_1") (pintype "power_in"))
    )
    (net (code "40") (name "/VBUS") (class "Default")
      (node (ref "C30") (pin "1") (pinfunction "1_1") (pintype "passive"))
      (node (ref "D1") (pin "A") (pinfunction "A_A") (pintype "passive"))
      (node (ref "J1") (pin "VBUS1") (pinfunction "VBUS_VBUS1") (pintype "bidirectional"))
      (node (ref "J1") (pin "VBUS2") (pinfunction "VBUS_VBUS2") (pintype "bidirectional"))
      (node (ref "R42") (pin "1") (pinfunction "1_1") (pintype "passive"))
    )
    (net (code "41") (name "/YLA") (class "Default")
      (node (ref "U$1") (pin "P$26") (pinfunction "SA_2_P$26") (pintype "output"))
      (node (ref "U$1") (pin "P$9") (pinfunction "SA_P$9") (pintype "output"))
      (node (ref "U$2") (pin "P$3") (pinfunction "C_P$3") (pintype "input"))
    )
    (net (code "42") (name "/YLB") (class "Default")
      (node (ref "U$1") (pin "P$11") (pinfunction "SB_P$11") (pintype "output"))
      (node (ref "U$1") (pin "P$24") (pinfunction "SB_2_P$24") (pintype "output"))
      (node (ref "U$2") (pin "P$2") (pinfunction "B_P$2") (pintype "input"))
    )
    (net (code "43") (name "/YLC") (class "Default")
      (node (ref "U$1") (pin "P$13") (pinfunction "SC_P$13") (pintype "output"))
      (node (ref "U$1") (pin "P$22") (pinfunction "SC_2_P$22") (pintype "output"))
      (node (ref "U$2") (pin "P$1") (pinfunction "A_P$1") (pintype "input"))
    )
    (net (code "44") (name "/YRA") (class "Default")
      (node (ref "U$3") (pin "P$26") (pinfunction "SA_2_P$26") (pintype "output"))
      (node (ref "U$3") (pin "P$9") (pinfunction "SA_P$9") (pintype "output"))
      (node (ref "U$4") (pin "P$3") (pinfunction "C_P$3") (pintype "input"))
    )
    (net (code "45") (name "/YRB") (class "Default")
      (node (ref "U$3") (pin "P$11") (pinfunction "SB_P$11") (pintype "output"))
      (node (ref "U$3") (pin "P$24") (pinfunction "SB_2_P$24") (pintype "output"))
      (node (ref "U$4") (pin "P$2") (pinfunction "B_P$2") (pintype "input"))
    )
    (net (code "46") (name "/YRC") (class "Default")
      (node (ref "U$3") (pin "P$13") (pinfunction "SC_P$13") (pintype "output"))
      (node (ref "U$3") (pin "P$22") (pinfunction "SC_2_P$22") (pintype "output"))
      (node (ref "U$4") (pin "P$1") (pinfunction "A_P$1") (pintype "input"))
    )
    (net (code "47") (name "GND") (class "Default")
      (node (ref "BATT") (pin "1") (pinfunction "1_1") (pintype "passive"))
      (node (ref "BOOT") (pin "1") (pinfunction "1_1") (pintype "passive"))
      (node (ref "C1") (pin "2") (pinfunction "2_2") (pintype "passive"))
      (node (ref "C10") (pin "-") (pinfunction "-_-") (pintype "passive"))
      (node (ref "C11") (pin "-") (pinfunction "-_-") (pintype "passive"))
      (node (ref "C13") (pin "1") (pinfunction "1_1") (pintype "passive"))
      (node (ref "C14") (pin "1") (pinfunction "1_1") (pintype "passive"))
      (node (ref "C15") (pin "1") (pinfunction "1_1") (pintype "passive"))
      (node (ref "C16") (pin "1") (pinfunction "1_1") (pintype "passive"))
      (node (ref "C17") (pin "1") (pinfunction "1_1") (pintype "passive"))
      (node (ref "C18") (pin "2") (pinfunction "2_2") (pintype "passive"))
      (node (ref "C19") (pin "2") (pinfunction "2_2") (pintype "passive"))
      (node (ref "C2") (pin "2") (pinfunction "2_2") (pintype "passive"))
      (node (ref "C20") (pin "2") (pinfunction "2_2") (pintype "passive"))
      (node (ref "C21") (pin "2") (pinfunction "2_2") (pintype "passive"))
      (node (ref "C22") (pin "1") (pinfunction "1_1") (pintype "passive"))
      (node (ref "C25") (pin "1") (pinfunction "1_1") (pintype "passive"))
      (node (ref "C28") (pin "1") (pinfunction "1_1") (pintype "passive"))
      (node (ref "C29") (pin "2") (pinfunction "2_2") (pintype "passive"))
      (node (ref "C3") (pin "2") (pinfunction "2_2") (pintype "passive"))
      (node (ref "C30") (pin "2") (pinfunction "2_2") (pintype "passive"))
      (node (ref "C4") (pin "2") (pinfunction "2_2") (pintype "passive"))
      (node (ref "C5") (pin "2") (pinfunction "2_2") (pintype "passive"))
      (node (ref "C6") (pin "2") (pinfunction "2_2") (pintype "passive"))
      (node (ref "C7") (pin "2") (pinfunction "2_2") (pintype "passive"))
      (node (ref "C8") (pin "2") (pinfunction "2_2") (pintype "passive"))
      (node (ref "C9") (pin "2") (pinfunction "2_2") (pintype "passive"))
      (node (ref "DEBUG") (pin "1") (pinfunction "1_1") (pintype "bidirectional"))
      (node (ref "J1") (pin "GND") (pinfunction "GND_GND") (pintype "bidirectional"))
      (node (ref "J1") (pin "GND2") (pinfunction "GND_GND2") (pintype "bidirectional"))
      (node (ref "J1") (pin "SHLD1") (pinfunction "SHLD_SHLD1") (pintype "bidirectional"))
      (node (ref "J1") (pin "SHLD2") (pinfunction "SHLD_SHLD2") (pintype "bidirectional"))
      (node (ref "J1") (pin "SHLD3") (pinfunction "SHLD_SHLD3") (pintype "bidirectional"))
      (node (ref "J1") (pin "SHLD4") (pinfunction "SHLD_SHLD4") (pintype "bidirectional"))
      (node (ref "J2") (pin "1") (pinfunction "1_1") (pintype "passive"))
      (node (ref "J3") (pin "1") (pinfunction "1_1") (pintype "passive"))
      (node (ref "LED1") (pin "C") (pinfunction "C_C") (pintype "passive"))
      (node (ref "LED11") (pin "A") (pinfunction "A_A") (pintype "passive"))
      (node (ref "LED12") (pin "A") (pinfunction "A_A") (pintype "passive"))
      (node (ref "LED13") (pin "A") (pinfunction "A_A") (pintype "passive"))
      (node (ref "LED14") (pin "A") (pinfunction "A_A") (pintype "passive"))
      (node (ref "LED15") (pin "A") (pinfunction "A_A") (pintype "passive"))
      (node (ref "LED16") (pin "A") (pinfunction "A_A") (pintype "passive"))
      (node (ref "LED17") (pin "A") (pinfunction "A_A") (pintype "passive"))
      (node (ref "LED18") (pin "A") (pinfunction "A_A") (pintype "passive"))
      (node (ref "LED2") (pin "C") (pinfunction "C_C") (pintype "passive"))
      (node (ref "Q1") (pin "2") (pinfunction "S_2") (pintype "bidirectional"))
      (node (ref "R17") (pin "1") (pinfunction "1_1") (pintype "passive"))
      (node (ref "R18") (pin "1") (pinfunction "1_1") (pintype "passive"))
      (node (ref "R35") (pin "1") (pinfunction "1_1") (pintype "passive"))
      (node (ref "R41") (pin "2") (pinfunction "2_2") (pintype "passive"))
      (node (ref "R9") (pin "1") (pinfunction "1_1") (pintype "passive"))
      (node (ref "RESET") (pin "A2") (pinfunction "1_A2") (pintype "passive"))
      (node (ref "T2") (pin "2") (pinfunction "E_2") (pintype "passive"))
      (node (ref "TP3") (pin "TP") (pinfunction "TP_TP") (pintype "input"))
      (node (ref "TP4") (pin "TP") (pinfunction "TP_TP") (pintype "input"))
      (node (ref "U$1") (pin "P$10") (pinfunction "LSS_P$10") (pintype "passive"))
      (node (ref "U$1") (pin "P$12") (pinfunction "LSS_2_P$12") (pintype "passive"))
      (node (ref "U$1") (pin "P$15") (pinfunction "SOA_P$15") (pintype "output"))
      (node (ref "U$1") (pin "P$16") (pinfunction "SOB_P$16") (pintype "output"))
      (node (ref "U$1") (pin "P$17") (pinfunction "SOC_P$17") (pintype "output"))
      (node (ref "U$1") (pin "P$18") (pinfunction "GND_P$18") (pintype "passive"))
      (node (ref "U$11") (pin "P$1") (pinfunction "P$1_P$1") (pintype "bidirectional"))
      (node (ref "U$14") (pin "P$1") (pinfunction "P$1_P$1") (pintype "bidirectional"))
      (node (ref "U$3") (pin "P$10") (pinfunction "LSS_P$10") (pintype "passive"))
      (node (ref "U$3") (pin "P$12") (pinfunction "LSS_2_P$12") (pintype "passive"))
      (node (ref "U$3") (pin "P$15") (pinfunction "SOA_P$15") (pintype "output"))
      (node (ref "U$3") (pin "P$16") (pinfunction "SOB_P$16") (pintype "output"))
      (node (ref "U$3") (pin "P$17") (pinfunction "SOC_P$17") (pintype "output"))
      (node (ref "U$3") (pin "P$18") (pinfunction "GND_P$18") (pintype "passive"))
      (node (ref "U$6") (pin "P$1") (pinfunction "SDO/SA0_P$1") (pintype "bidirectional"))
      (node (ref "U$6") (pin "P$2") (pinfunction "SDX_P$2") (pintype "bidirectional"))
      (node (ref "U$6") (pin "P$3") (pinfunction "SCX_P$3") (pintype "bidirectional"))
      (node (ref "U$6") (pin "P$6") (pinfunction "GND1_P$6") (pintype "bidirectional"))
      (node (ref "U$6") (pin "P$7") (pinfunction "GND2_P$7") (pintype "bidirectional"))
      (node (ref "U$7") (pin "P$1") (pinfunction "P$1_P$1") (pintype "bidirectional"))
      (node (ref "U$9") (pin "P$1") (pinfunction "P$1_P$1") (pintype "bidirectional"))
      (node (ref "U2") (pin "4") (pinfunction "GND_4") (pintype "bidirectional"))
      (node (ref "U3") (pin "12") (pinfunction "VSSA_12") (pintype "power_in"))
      (node (ref "U3") (pin "18") (pinfunction "VSS_2_18") (pintype "power_in"))
      (node (ref "U3") (pin "31") (pinfunction "VSS_3_31") (pintype "power_in"))
      (node (ref "U3") (pin "47") (pinfunction "VSS_4_47") (pintype "power_in"))
      (node (ref "U3") (pin "63") (pinfunction "VSS_63") (pintype "power_in"))
      (node (ref "U4") (pin "2") (pinfunction "GND_2") (pintype "bidirectional"))
      (node (ref "U4") (pin "PAD") (pinfunction "GND_PAD") (pintype "bidirectional"))
      (node (ref "USER") (pin "A2") (pinfunction "1_A2") (pintype "passive"))
      (node (ref "X1") (pin "1") (pinfunction "1_1") (pintype "passive"))
      (node (ref "X1") (pin "19") (pinfunction "1_19") (pintype "passive"))
      (node (ref "X1") (pin "2") (pinfunction "1_2") (pintype "passive"))
      (node (ref "X1") (pin "20") (pinfunction "1_20") (pintype "passive"))
      (node (ref "X2") (pin "1") (pinfunction "1_1") (pintype "passive"))
      (node (ref "X2") (pin "19") (pinfunction "1_19") (pintype "passive"))
      (node (ref "X2") (pin "2") (pinfunction "1_2") (pintype "passive"))
      (node (ref "X2") (pin "20") (pinfunction "1_20") (pintype "passive"))
    )
    (net (code "48") (name "Net-(J1-CC1)") (class "Default")
      (node (ref "J1") (pin "A5") (pinfunction "CC1_A5") (pintype "bidirectional"))
      (node (ref "R18") (pin "2") (pinfunction "2_2") (pintype "passive"))
    )
    (net (code "49") (name "Net-(J1-CC2)") (class "Default")
      (node (ref "J1") (pin "B5") (pinfunction "CC2_B5") (pintype "bidirectional"))
      (node (ref "R17") (pin "2") (pinfunction "2_2") (pintype "passive"))
    )
    (net (code "50") (name "Net-(L1-1)") (class "Default")
      (node (ref "C12") (pin "2") (pinfunction "2_2") (pintype "passive"))
      (node (ref "L1") (pin "P$1") (pinfunction "1_P$1") (pintype "passive"))
      (node (ref "U2") (pin "5") (pinfunction "SW_5") (pintype "bidirectional"))
    )
    (net (code "51") (name "Net-(LED1-PadA)") (class "Default")
      (node (ref "LED1") (pin "A") (pinfunction "A_A") (pintype "passive"))
      (node (ref "R12") (pin "1") (pinfunction "1_1") (pintype "passive"))
    )
    (net (code "52") (name "Net-(LED2-PadA)") (class "Default")
      (node (ref "LED2") (pin "A") (pinfunction "A_A") (pintype "passive"))
      (node (ref "R13") (pin "1") (pinfunction "1_1") (pintype "passive"))
    )
    (net (code "53") (name "Net-(LED3-PadA)") (class "Default")
      (node (ref "LED3") (pin "A") (pinfunction "A_A") (pintype "passive"))
      (node (ref "R19") (pin "1") (pinfunction "1_1") (pintype "passive"))
    )
    (net (code "54") (name "Net-(LED4-PadA)") (class "Default")
      (node (ref "LED4") (pin "A") (pinfunction "A_A") (pintype "passive"))
      (node (ref "R20") (pin "1") (pinfunction "1_1") (pintype "passive"))
    )
    (net (code "55") (name "Net-(LED5-PadA)") (class "Default")
      (node (ref "LED5") (pin "A") (pinfunction "A_A") (pintype "passive"))
      (node (ref "R21") (pin "1") (pinfunction "1_1") (pintype "passive"))
    )
    (net (code "56") (name "Net-(LED6-PadA)") (class "Default")
      (node (ref "LED6") (pin "A") (pinfunction "A_A") (pintype "passive"))
      (node (ref "R22") (pin "1") (pinfunction "1_1") (pintype "passive"))
    )
    (net (code "57") (name "Net-(LED7-PadA)") (class "Default")
      (node (ref "LED7") (pin "A") (pinfunction "A_A") (pintype "passive"))
      (node (ref "R23") (pin "1") (pinfunction "1_1") (pintype "passive"))
    )
    (net (code "58") (name "Net-(LED8-PadA)") (class "Default")
      (node (ref "LED8") (pin "A") (pinfunction "A_A") (pintype "passive"))
      (node (ref "R24") (pin "1") (pinfunction "1_1") (pintype "passive"))
    )
    (net (code "59") (name "Net-(LED9-PadA)") (class "Default")
      (node (ref "LED9") (pin "A") (pinfunction "A_A") (pintype "passive"))
      (node (ref "R25") (pin "1") (pinfunction "1_1") (pintype "passive"))
    )
    (net (code "60") (name "Net-(LED10-PadA)") (class "Default")
      (node (ref "LED10") (pin "A") (pinfunction "A_A") (pintype "passive"))
      (node (ref "R26") (pin "1") (pinfunction "1_1") (pintype "passive"))
    )
    (net (code "61") (name "Net-(Q1-D)") (class "Default")
      (node (ref "LED10") (pin "C") (pinfunction "C_C") (pintype "passive"))
      (node (ref "LED3") (pin "C") (pinfunction "C_C") (pintype "passive"))
      (node (ref "LED4") (pin "C") (pinfunction "C_C") (pintype "passive"))
      (node (ref "LED5") (pin "C") (pinfunction "C_C") (pintype "passive"))
      (node (ref "LED6") (pin "C") (pinfunction "C_C") (pintype "passive"))
      (node (ref "LED7") (pin "C") (pinfunction "C_C") (pintype "passive"))
      (node (ref "LED8") (pin "C") (pinfunction "C_C") (pintype "passive"))
      (node (ref "LED9") (pin "C") (pinfunction "C_C") (pintype "passive"))
      (node (ref "Q1") (pin "3") (pinfunction "D_3") (pintype "bidirectional"))
    )
    (net (code "62") (name "Net-(R5-Pad2)") (class "Default")
      (node (ref "R5") (pin "2") (pinfunction "2_2") (pintype "passive"))
      (node (ref "U$10") (pin "P$2") (pinfunction "P$2_P$2") (pintype "bidirectional"))
    )
    (net (code "63") (name "Net-(R6-Pad2)") (class "Default")
      (node (ref "R6") (pin "2") (pinfunction "2_2") (pintype "passive"))
      (node (ref "U$13") (pin "P$2") (pinfunction "P$2_P$2") (pintype "bidirectional"))
    )
    (net (code "64") (name "Net-(R7-Pad2)") (class "Default")
      (node (ref "R7") (pin "2") (pinfunction "2_2") (pintype "passive"))
      (node (ref "U$12") (pin "P$2") (pinfunction "P$2_P$2") (pintype "bidirectional"))
    )
    (net (code "65") (name "Net-(R8-Pad2)") (class "Default")
      (node (ref "R8") (pin "2") (pinfunction "2_2") (pintype "passive"))
      (node (ref "U$8") (pin "P$2") (pinfunction "P$2_P$2") (pintype "bidirectional"))
    )
    (net (code "66") (name "Net-(T2-B)") (class "Default")
      (node (ref "R9") (pin "2") (pinfunction "2_2") (pintype "passive"))
      (node (ref "T1") (pin "E") (pinfunction "E_E") (pintype "passive"))
      (node (ref "T2") (pin "1") (pinfunction "B_1") (pintype "passive"))
      (node (ref "TP2") (pin "TP") (pinfunction "TP_TP") (pintype "input"))
    )
    (net (code "67") (name "Net-(T2-C)") (class "Default")
      (node (ref "R10") (pin "1") (pinfunction "1_1") (pintype "passive"))
      (node (ref "T1") (pin "B") (pinfunction "B_B") (pintype "passive"))
      (node (ref "T2") (pin "3") (pinfunction "C_3") (pintype "passive"))
    )
    (net (code "68") (name "Net-(U$1-CP1)") (class "Default")
      (node (ref "C23") (pin "2") (pinfunction "2_2") (pintype "passive"))
      (node (ref "U$1") (pin "P$20") (pinfunction "CP1_P$20") (pintype "passive"))
    )
    (net (code "69") (name "Net-(U$1-CP2)") (class "Default")
      (node (ref "C23") (pin "1") (pinfunction "1_1") (pintype "passive"))
      (node (ref "U$1") (pin "P$21") (pinfunction "CP2_P$21") (pintype "passive"))
    )
    (net (code "70") (name "Net-(U$1-VCP)") (class "Default")
      (node (ref "C24") (pin "2") (pinfunction "2_2") (pintype "passive"))
      (node (ref "U$1") (pin "P$19") (pinfunction "VCP_P$19") (pintype "output"))
    )
    (net (code "71") (name "Net-(U$1-VG)") (class "Default")
      (node (ref "C25") (pin "2") (pinfunction "2_2") (pintype "passive"))
      (node (ref "U$1") (pin "P$14") (pinfunction "VG_P$14") (pintype "power_in"))
    )
    (net (code "72") (name "Net-(U$3-CP1)") (class "Default")
      (node (ref "C26") (pin "2") (pinfunction "2_2") (pintype "passive"))
      (node (ref "U$3") (pin "P$20") (pinfunction "CP1_P$20") (pintype "passive"))
    )
    (net (code "73") (name "Net-(U$3-CP2)") (class "Default")
      (node (ref "C26") (pin "1") (pinfunction "1_1") (pintype "passive"))
      (node (ref "U$3") (pin "P$21") (pinfunction "CP2_P$21") (pintype "passive"))
    )
    (net (code "74") (name "Net-(U$3-VCP)") (class "Default")
      (node (ref "C27") (pin "2") (pinfunction "2_2") (pintype "passive"))
      (node (ref "U$3") (pin "P$19") (pinfunction "VCP_P$19") (pintype "output"))
    )
    (net (code "75") (name "Net-(U$3-VG)") (class "Default")
      (node (ref "C28") (pin "2") (pinfunction "2_2") (pintype "passive"))
      (node (ref "U$3") (pin "P$14") (pinfunction "VG_P$14") (pintype "power_in"))
    )
    (net (code "76") (name "Net-(U2-BST)") (class "Default")
      (node (ref "C12") (pin "1") (pinfunction "1_1") (pintype "passive"))
      (node (ref "U2") (pin "6") (pinfunction "BST_6") (pintype "bidirectional"))
    )
    (net (code "77") (name "Net-(U3A-PH0-OSC_IN)") (class "Default")
      (node (ref "C20") (pin "1") (pinfunction "1_1") (pintype "passive"))
      (node (ref "U3") (pin "5") (pinfunction "PH0-OSC_IN_5") (pintype "bidirectional"))
      (node (ref "Y1") (pin "3") (pinfunction "2_3") (pintype "passive"))
    )
    (net (code "78") (name "Net-(U3A-PH1-OSC_OUT)") (class "Default")
      (node (ref "C21") (pin "1") (pinfunction "1_1") (pintype "passive"))
      (node (ref "U3") (pin "6") (pinfunction "PH1-OSC_OUT_6") (pintype "bidirectional"))
      (node (ref "Y1") (pin "1") (pinfunction "1_1") (pintype "passive"))
    )
    (net (code "79") (name "Net-(U3B-VCAP_1)") (class "Default")
      (node (ref "C22") (pin "2") (pinfunction "2_2") (pintype "passive"))
      (node (ref "U3") (pin "30") (pinfunction "VCAP_1_30") (pintype "power_in"))
    )
    (net (code "80") (name "Net-(U4-DTR)") (class "Default")
      (node (ref "SJ1") (pin "1") (pinfunction "1_1") (pintype "passive"))
      (node (ref "U4") (pin "23") (pinfunction "DTR_23") (pintype "bidirectional"))
    )
    (net (code "81") (name "Net-(U4-RTS)") (class "Default")
      (node (ref "SJ2") (pin "1") (pinfunction "1_1") (pintype "passive"))
      (node (ref "U4") (pin "19") (pinfunction "RTS_19") (pintype "bidirectional"))
    )
    (net (code "82") (name "Net-(U4-VBUS)") (class "Default")
      (node (ref "R41") (pin "1") (pinfunction "1_1") (pintype "passive"))
      (node (ref "R42") (pin "2") (pinfunction "2_2") (pintype "passive"))
      (node (ref "U4") (pin "8") (pinfunction "VBUS_8") (pintype "bidirectional"))
    )
    (net (code "83") (name "Net-(U4-~{RSTB})") (class "Default")
      (node (ref "R40") (pin "2") (pinfunction "2_2") (pintype "passive"))
      (node (ref "U4") (pin "9") (pinfunction "~{RSTB}_9") (pintype "bidirectional"))
    )
    (net (code "84") (name "VCC") (class "Default")
      (node (ref "BATT") (pin "2") (pinfunction "2_2") (pintype "passive"))
      (node (ref "C10") (pin "+") (pinfunction "+_+") (pintype "passive"))
      (node (ref "C11") (pin "+") (pinfunction "+_+") (pintype "passive"))
      (node (ref "C13") (pin "2") (pinfunction "2_2") (pintype "passive"))
      (node (ref "C14") (pin "2") (pinfunction "2_2") (pintype "passive"))
      (node (ref "C24") (pin "1") (pinfunction "1_1") (pintype "passive"))
      (node (ref "C27") (pin "1") (pinfunction "1_1") (pintype "passive"))
      (node (ref "C4") (pin "1") (pinfunction "1_1") (pintype "passive"))
      (node (ref "C5") (pin "1") (pinfunction "1_1") (pintype "passive"))
      (node (ref "C6") (pin "1") (pinfunction "1_1") (pintype "passive"))
      (node (ref "C7") (pin "1") (pinfunction "1_1") (pintype "passive"))
      (node (ref "D1") (pin "C") (pinfunction "C_C") (pintype "passive"))
      (node (ref "U$1") (pin "P$23") (pinfunction "VIN_2_P$23") (pintype "power_in"))
      (node (ref "U$1") (pin "P$25") (pinfunction "VIN_P$25") (pintype "power_in"))
      (node (ref "U$10") (pin "P$1") (pinfunction "P$1_P$1") (pintype "bidirectional"))
      (node (ref "U$12") (pin "P$1") (pinfunction "P$1_P$1") (pintype "bidirectional"))
      (node (ref "U$13") (pin "P$1") (pinfunction "P$1_P$1") (pintype "bidirectional"))
      (node (ref "U$3") (pin "P$23") (pinfunction "VIN_2_P$23") (pintype "power_in"))
      (node (ref "U$3") (pin "P$25") (pinfunction "VIN_P$25") (pintype "power_in"))
      (node (ref "U$8") (pin "P$1") (pinfunction "P$1_P$1") (pintype "bidirectional"))
      (node (ref "U2") (pin "2") (pinfunction "EN_2") (pintype "bidirectional"))
      (node (ref "U2") (pin "3") (pinfunction "VIN_3") (pintype "bidirectional"))
      (node (ref "X1") (pin "3") (pinfunction "1_3") (pintype "passive"))
      (node (ref "X2") (pin "18") (pinfunction "1_18") (pintype "passive"))
    )
    (net (code "85") (name "unconnected-(U$1-NFAULT-PadP$1)") (class "Default")
      (node (ref "U$1") (pin "P$1") (pinfunction "NFAULT_P$1") (pintype "output"))
    )
    (net (code "86") (name "unconnected-(U$3-NFAULT-PadP$1)") (class "Default")
      (node (ref "U$3") (pin "P$1") (pinfunction "NFAULT_P$1") (pintype "output"))
    )
    (net (code "87") (name "unconnected-(U$6-INT1-PadP$4)") (class "Default")
      (node (ref "U$6") (pin "P$4") (pinfunction "INT1_P$4") (pintype "bidirectional"))
    )
    (net (code "88") (name "unconnected-(U$6-INT2-PadP$9)") (class "Default")
      (node (ref "U$6") (pin "P$9") (pinfunction "INT2_P$9") (pintype "bidirectional"))
    )
    (net (code "89") (name "unconnected-(U$6-NC1-PadP$10)") (class "Default")
      (node (ref "U$6") (pin "P$10") (pinfunction "NC1_P$10") (pintype "bidirectional"))
    )
    (net (code "90") (name "unconnected-(U$6-NC2-PadP$11)") (class "Default")
      (node (ref "U$6") (pin "P$11") (pinfunction "NC2_P$11") (pintype "bidirectional"))
    )
    (net (code "91") (name "unconnected-(U3A-PA8-Pad41)") (class "Default")
      (node (ref "U3") (pin "41") (pinfunction "PA8_41") (pintype "bidirectional"))
    )
    (net (code "92") (name "unconnected-(U3A-PA11-Pad44)") (class "Default")
      (node (ref "U3") (pin "44") (pinfunction "PA11_44") (pintype "bidirectional"))
    )
    (net (code "93") (name "unconnected-(U3A-PA12-Pad45)") (class "Default")
      (node (ref "U3") (pin "45") (pinfunction "PA12_45") (pintype "bidirectional"))
    )
    (net (code "94") (name "unconnected-(U3A-PA13-Pad46)") (class "Default")
      (node (ref "U3") (pin "46") (pinfunction "PA13_46") (pintype "bidirectional"))
    )
    (net (code "95") (name "unconnected-(U3A-PA14-Pad49)") (class "Default")
      (node (ref "U3") (pin "49") (pinfunction "PA14_49") (pintype "bidirectional"))
    )
    (net (code "96") (name "unconnected-(U3A-PA15-Pad50)") (class "Default")
      (node (ref "U3") (pin "50") (pinfunction "PA15_50") (pintype "bidirectional"))
    )
    (net (code "97") (name "unconnected-(U3A-PB3-Pad55)") (class "Default")
      (node (ref "U3") (pin "55") (pinfunction "PB3_55") (pintype "bidirectional"))
    )
    (net (code "98") (name "unconnected-(U3A-PB4-Pad56)") (class "Default")
      (node (ref "U3") (pin "56") (pinfunction "PB4_56") (pintype "bidirectional"))
    )
    (net (code "99") (name "unconnected-(U3A-PB12-Pad33)") (class "Default")
      (node (ref "U3") (pin "33") (pinfunction "PB12_33") (pintype "bidirectional"))
    )
    (net (code "100") (name "unconnected-(U3A-PB13-Pad34)") (class "Default")
      (node (ref "U3") (pin "34") (pinfunction "PB13_34") (pintype "bidirectional"))
    )
    (net (code "101") (name "unconnected-(U3A-PB14-Pad35)") (class "Default")
      (node (ref "U3") (pin "35") (pinfunction "PB14_35") (pintype "bidirectional"))
    )
    (net (code "102") (name "unconnected-(U3A-PB15-Pad36)") (class "Default")
      (node (ref "U3") (pin "36") (pinfunction "PB15_36") (pintype "bidirectional"))
    )
    (net (code "103") (name "unconnected-(U3A-PC13-Pad2)") (class "Default")
      (node (ref "U3") (pin "2") (pinfunction "PC13_2") (pintype "bidirectional"))
    )
    (net (code "104") (name "unconnected-(U3A-PC14-OSC32_IN-Pad3)") (class "Default")
      (node (ref "U3") (pin "3") (pinfunction "PC14-OSC32_IN_3") (pintype "bidirectional"))
    )
    (net (code "105") (name "unconnected-(U3A-PC15-OSC32_OUT-Pad4)") (class "Default")
      (node (ref "U3") (pin "4") (pinfunction "PC15-OSC32_OUT_4") (pintype "bidirectional"))
    )
    (net (code "106") (name "unconnected-(U3A-PD2-Pad54)") (class "Default")
      (node (ref "U3") (pin "54") (pinfunction "PD2_54") (pintype "bidirectional"))
    )
    (net (code "107") (name "unconnected-(U4-CTS-Pad18)") (class "Default")
      (node (ref "U4") (pin "18") (pinfunction "CTS_18") (pintype "bidirectional"))
    )
    (net (code "108") (name "unconnected-(U4-DCD-Pad24)") (class "Default")
      (node (ref "U4") (pin "24") (pinfunction "DCD_24") (pintype "bidirectional"))
    )
    (net (code "109") (name "unconnected-(U4-DSR-Pad22)") (class "Default")
      (node (ref "U4") (pin "22") (pinfunction "DSR_22") (pintype "bidirectional"))
    )
    (net (code "110") (name "unconnected-(U4-GPIO0{slash}TXT-Pad14)") (class "Default")
      (node (ref "U4") (pin "14") (pinfunction "GPIO0/TXT_14") (pintype "bidirectional"))
    )
    (net (code "111") (name "unconnected-(U4-GPIO1{slash}RXT-Pad13)") (class "Default")
      (node (ref "U4") (pin "13") (pinfunction "GPIO1/RXT_13") (pintype "bidirectional"))
    )
    (net (code "112") (name "unconnected-(U4-GPIO2{slash}RS485-Pad12)") (class "Default")
      (node (ref "U4") (pin "12") (pinfunction "GPIO2/RS485_12") (pintype "bidirectional"))
    )
    (net (code "113") (name "unconnected-(U4-GPIO3{slash}WAKEUP-Pad11)") (class "Default")
      (node (ref "U4") (pin "11") (pinfunction "GPIO3/WAKEUP_11") (pintype "bidirectional"))
    )
    (net (code "114") (name "unconnected-(U4-SUSPEND-Pad17)") (class "Default")
      (node (ref "U4") (pin "17") (pinfunction "SUSPEND_17") (pintype "bidirectional"))
    )
    (net (code "115") (name "unconnected-(U4-SUSPENDB-Pad15)") (class "Default")
      (node (ref "U4") (pin "15") (pinfunction "SUSPENDB_15") (pintype "bidirectional"))
    )
    (net (code "116") (name "unconnected-(U4-~{RI}{slash}CLK-Pad1)") (class "Default")
      (node (ref "U4") (pin "1") (pinfunction "~{RI}/CLK_1") (pintype "bidirectional"))
    )
    (net (code "117") (name "unconnected-(X2B-1-Pad10)") (class "Default")
      (node (ref "X2") (pin "10") (pinfunction "1_10") (pintype "passive"))
    )
    (net (code "118") (name "unconnected-(X2C-1-Pad11)") (class "Default")
      (node (ref "X2") (pin "11") (pinfunction "1_11") (pintype "passive"))
    )
    (net (code "119") (name "unconnected-(X2D-1-Pad12)") (class "Default")
      (node (ref "X2") (pin "12") (pinfunction "1_12") (pintype "passive"))
    )
    (net (code "120") (name "unconnected-(X2E-1-Pad13)") (class "Default")
      (node (ref "X2") (pin "13") (pinfunction "1_13") (pintype "passive"))
    )
    (net (code "121") (name "unconnected-(X2F-1-Pad14)") (class "Default")
      (node (ref "X2") (pin "14") (pinfunction "1_14") (pintype "passive"))
    )
    (net (code "122") (name "unconnected-(X2G-1-Pad15)") (class "Default")
      (node (ref "X2") (pin "15") (pinfunction "1_15") (pintype "passive"))
    )
    (net (code "123") (name "unconnected-(X2H-1-Pad16)") (class "Default")
      (node (ref "X2") (pin "16") (pinfunction "1_16") (pintype "passive"))
    )
    (net (code "124") (name "unconnected-(X2P-1-Pad5)") (class "Default")
      (node (ref "X2") (pin "5") (pinfunction "1_5") (pintype "passive"))
    )
    (net (code "125") (name "unconnected-(X2Q-1-Pad6)") (class "Default")
      (node (ref "X2") (pin "6") (pinfunction "1_6") (pintype "passive"))
    )
    (net (code "126") (name "unconnected-(X2R-1-Pad7)") (class "Default")
      (node (ref "X2") (pin "7") (pinfunction "1_7") (pintype "passive"))
    )
    (net (code "127") (name "unconnected-(X2S-1-Pad8)") (class "Default")
      (node (ref "X2") (pin "8") (pinfunction "1_8") (pintype "passive"))
    )
    (net (code "128") (name "unconnected-(X2T-1-Pad9)") (class "Default")
      (node (ref "X2") (pin "9") (pinfunction "1_9") (pintype "passive"))
    )
  )
)
